# Siscom_Seguidor_1.net
KiCad netlist of a schematic drawn in EAGLE
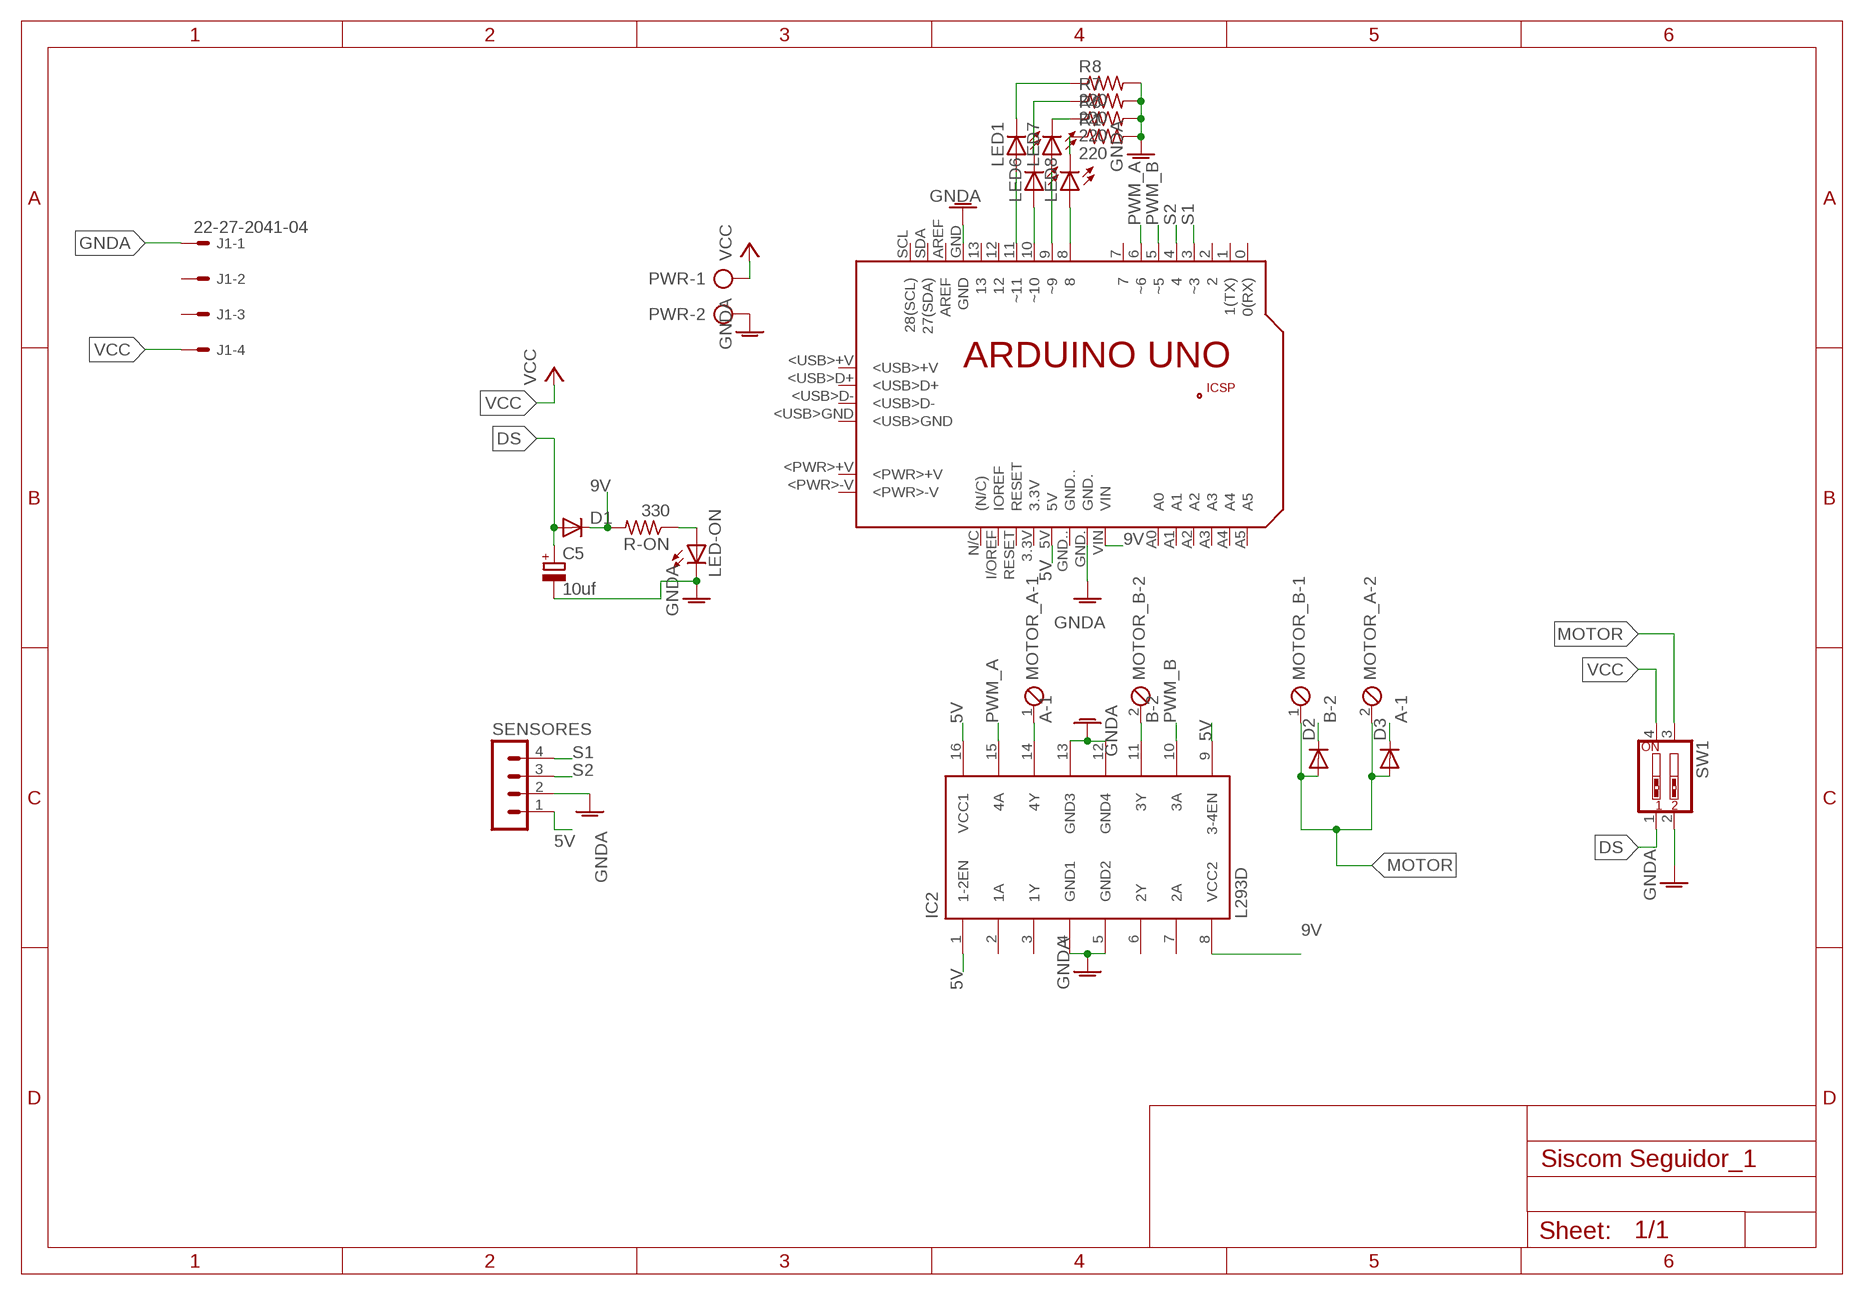
[diagram p0: schematic, sheet 1]

(export (version "E")
  (design (tool "Eeschema 10.0.6"))
  (components
    (comp (ref "C5")
      (value "10uf")
      (footprint "eagle-import:E2,5-6E")
      (libsource (lib "eagle-import") (part "CPOL-EUE2,5-6E"))
    )
    (comp (ref "D1")
      (value "1N4148DO35-7")
      (footprint "eagle-import:DO35-7")
      (libsource (lib "eagle-import") (part "1N4148DO35-7"))
    )
    (comp (ref "D2")
      (value "1N4148DO35-7")
      (footprint "eagle-import:DO35-7")
      (libsource (lib "eagle-import") (part "1N4148DO35-7"))
    )
    (comp (ref "D3")
      (value "1N4148DO35-7")
      (footprint "eagle-import:DO35-7")
      (libsource (lib "eagle-import") (part "1N4148DO35-7"))
    )
    (comp (ref "IC2")
      (value "L293D")
      (footprint "eagle-import:DIL16")
      (libsource (lib "eagle-import") (part "L293D"))
    )
    (comp (ref "J1")
      (value "22-27-2041-04")
      (footprint "eagle-import:6410-04")
      (libsource (lib "eagle-import") (part "22-?-0427-2041"))
    )
    (comp (ref "LED-ON")
      (value "LED3MM")
      (footprint "eagle-import:LED3MM")
      (libsource (lib "eagle-import") (part "LED3MM"))
    )
    (comp (ref "LED1")
      (value "LED3MM")
      (footprint "eagle-import:LED3MM")
      (libsource (lib "eagle-import") (part "LED3MM"))
    )
    (comp (ref "LED6")
      (value "LED3MM")
      (footprint "eagle-import:LED3MM")
      (libsource (lib "eagle-import") (part "LED3MM"))
    )
    (comp (ref "LED7")
      (value "LED3MM")
      (footprint "eagle-import:LED3MM")
      (libsource (lib "eagle-import") (part "LED3MM"))
    )
    (comp (ref "LED8")
      (value "LED3MM")
      (footprint "eagle-import:LED3MM")
      (libsource (lib "eagle-import") (part "LED3MM"))
    )
    (comp (ref "MOTOR_A")
      (value "MPT2")
      (footprint "eagle-import:2POL254")
      (libsource (lib "eagle-import") (part "MPT2"))
    )
    (comp (ref "MOTOR_B")
      (value "MPT2")
      (footprint "eagle-import:2POL254")
      (libsource (lib "eagle-import") (part "MPT2"))
    )
    (comp (ref "PCB2")
      (value "ARDUINO_UNO")
      (footprint "eagle-import:ARDUINO_UNO")
      (libsource (lib "eagle-import") (part "ARDUINO_UNO"))
    )
    (comp (ref "PWR")
      (value "AK500/2")
      (footprint "eagle-import:AK500_2")
      (libsource (lib "eagle-import") (part "AK500/2"))
    )
    (comp (ref "R-ON")
      (value "330")
      (footprint "eagle-import:0204_7")
      (libsource (lib "eagle-import") (part "R-US_0204/7"))
    )
    (comp (ref "R1")
      (value "220")
      (footprint "eagle-import:0204_7")
      (libsource (lib "eagle-import") (part "R-US_0204/7"))
    )
    (comp (ref "R6")
      (value "220")
      (footprint "eagle-import:0204_7")
      (libsource (lib "eagle-import") (part "R-US_0204/7"))
    )
    (comp (ref "R7")
      (value "220")
      (footprint "eagle-import:0204_7")
      (libsource (lib "eagle-import") (part "R-US_0204/7"))
    )
    (comp (ref "R8")
      (value "220")
      (footprint "eagle-import:0204_7")
      (libsource (lib "eagle-import") (part "R-US_0204/7"))
    )
    (comp (ref "SENSORES")
      (value "MA04-1")
      (footprint "eagle-import:MA04-1")
      (libsource (lib "eagle-import") (part "MA04-1"))
    )
    (comp (ref "SW1")
      (value "SW_DIP-2")
      (footprint "eagle-import:EDG-02")
      (libsource (lib "eagle-import") (part "SW_DIP-2"))
    )
  )
  (nets
    (net (code "1") (name "/5V") (class "Default")
      (node (ref "IC2") (pin "1") (pinfunction "1-2EN_1") (pintype "input"))
      (node (ref "IC2") (pin "16") (pinfunction "VCC1_16") (pintype "power_in"))
      (node (ref "IC2") (pin "9") (pinfunction "3-4EN_9") (pintype "input"))
      (node (ref "PCB2") (pin "5V") (pinfunction "5V_5V") (pintype "bidirectional"))
      (node (ref "SENSORES") (pin "1") (pinfunction "1_1") (pintype "passive"))
    )
    (net (code "2") (name "/9V") (class "Default")
      (node (ref "D1") (pin "C") (pinfunction "C_C") (pintype "passive"))
      (node (ref "IC2") (pin "8") (pinfunction "VCC2_8") (pintype "power_in"))
      (node (ref "PCB2") (pin "VIN") (pinfunction "VIN_VIN") (pintype "bidirectional"))
      (node (ref "R-ON") (pin "2") (pinfunction "2_2") (pintype "passive"))
    )
    (net (code "3") (name "/A-1") (class "Default")
      (node (ref "D3") (pin "C") (pinfunction "C_C") (pintype "passive"))
      (node (ref "IC2") (pin "14") (pinfunction "4Y_14") (pintype "output"))
      (node (ref "MOTOR_A") (pin "1") (pinfunction "1_1") (pintype "passive"))
    )
    (net (code "4") (name "/B-2") (class "Default")
      (node (ref "D2") (pin "C") (pinfunction "C_C") (pintype "passive"))
      (node (ref "IC2") (pin "11") (pinfunction "3Y_11") (pintype "output"))
      (node (ref "MOTOR_B") (pin "2") (pinfunction "1_2") (pintype "passive"))
    )
    (net (code "5") (name "/PWM_A") (class "Default")
      (node (ref "IC2") (pin "15") (pinfunction "4A_15") (pintype "input"))
      (node (ref "PCB2") (pin "6") (pinfunction "~{6}_6") (pintype "bidirectional"))
    )
    (net (code "6") (name "/PWM_B") (class "Default")
      (node (ref "IC2") (pin "10") (pinfunction "3A_10") (pintype "input"))
      (node (ref "PCB2") (pin "5") (pinfunction "~{5}_5") (pintype "bidirectional"))
    )
    (net (code "7") (name "/S1") (class "Default")
      (node (ref "PCB2") (pin "3") (pinfunction "~{3}_3") (pintype "bidirectional"))
      (node (ref "SENSORES") (pin "4") (pinfunction "4_4") (pintype "passive"))
    )
    (net (code "8") (name "/S2") (class "Default")
      (node (ref "PCB2") (pin "4") (pinfunction "4_4") (pintype "bidirectional"))
      (node (ref "SENSORES") (pin "3") (pinfunction "3_3") (pintype "passive"))
    )
    (net (code "9") (name "DS") (class "Default")
      (node (ref "C5") (pin "+") (pinfunction "+_+") (pintype "passive"))
      (node (ref "D1") (pin "A") (pinfunction "A_A") (pintype "passive"))
      (node (ref "SW1") (pin "1") (pinfunction "1_1") (pintype "passive"))
    )
    (net (code "10") (name "GNDA") (class "Default")
      (node (ref "C5") (pin "-") (pinfunction "-_-") (pintype "passive"))
      (node (ref "IC2") (pin "12") (pinfunction "GND4_12") (pintype "power_in"))
      (node (ref "IC2") (pin "13") (pinfunction "GND3_13") (pintype "power_in"))
      (node (ref "IC2") (pin "4") (pinfunction "GND1_4") (pintype "power_in"))
      (node (ref "IC2") (pin "5") (pinfunction "GND2_5") (pintype "power_in"))
      (node (ref "J1") (pin "1") (pinfunction "S_1") (pintype "passive"))
      (node (ref "LED-ON") (pin "K") (pinfunction "C_K") (pintype "passive"))
      (node (ref "PCB2") (pin "GND") (pinfunction "GND_GND") (pintype "bidirectional"))
      (node (ref "PCB2") (pin "GND.") (pinfunction "GND._GND.") (pintype "bidirectional"))
      (node (ref "PWR") (pin "2") (pinfunction "KL_2") (pintype "passive"))
      (node (ref "R1") (pin "2") (pinfunction "2_2") (pintype "passive"))
      (node (ref "R6") (pin "2") (pinfunction "2_2") (pintype "passive"))
      (node (ref "R7") (pin "2") (pinfunction "2_2") (pintype "passive"))
      (node (ref "R8") (pin "2") (pinfunction "2_2") (pintype "passive"))
      (node (ref "SENSORES") (pin "2") (pinfunction "2_2") (pintype "passive"))
      (node (ref "SW1") (pin "2") (pinfunction "2_2") (pintype "passive"))
    )
    (net (code "11") (name "MOTOR") (class "Default")
      (node (ref "D2") (pin "A") (pinfunction "A_A") (pintype "passive"))
      (node (ref "D3") (pin "A") (pinfunction "A_A") (pintype "passive"))
      (node (ref "MOTOR_A") (pin "2") (pinfunction "1_2") (pintype "passive"))
      (node (ref "MOTOR_B") (pin "1") (pinfunction "1_1") (pintype "passive"))
      (node (ref "SW1") (pin "3") (pinfunction "3_3") (pintype "passive"))
    )
    (net (code "12") (name "Net-(LED-ON-PadA)") (class "Default")
      (node (ref "LED-ON") (pin "A") (pinfunction "A_A") (pintype "passive"))
      (node (ref "R-ON") (pin "1") (pinfunction "1_1") (pintype "passive"))
    )
    (net (code "13") (name "Net-(LED1-C)") (class "Default")
      (node (ref "LED1") (pin "K") (pinfunction "C_K") (pintype "passive"))
      (node (ref "R8") (pin "1") (pinfunction "1_1") (pintype "passive"))
    )
    (net (code "14") (name "Net-(LED6-C)") (class "Default")
      (node (ref "LED6") (pin "K") (pinfunction "C_K") (pintype "passive"))
      (node (ref "R7") (pin "1") (pinfunction "1_1") (pintype "passive"))
    )
    (net (code "15") (name "Net-(LED7-C)") (class "Default")
      (node (ref "LED7") (pin "K") (pinfunction "C_K") (pintype "passive"))
      (node (ref "R6") (pin "1") (pinfunction "1_1") (pintype "passive"))
    )
    (net (code "16") (name "Net-(LED8-C)") (class "Default")
      (node (ref "LED8") (pin "K") (pinfunction "C_K") (pintype "passive"))
      (node (ref "R1") (pin "1") (pinfunction "1_1") (pintype "passive"))
    )
    (net (code "17") (name "Net-(LED8-PadA)") (class "Default")
      (node (ref "LED8") (pin "A") (pinfunction "A_A") (pintype "passive"))
      (node (ref "PCB2") (pin "8") (pinfunction "8_8") (pintype "bidirectional"))
    )
    (net (code "18") (name "Net-(PCB2-~{9})") (class "Default")
      (node (ref "LED7") (pin "A") (pinfunction "A_A") (pintype "passive"))
      (node (ref "PCB2") (pin "9") (pinfunction "~{9}_9") (pintype "bidirectional"))
    )
    (net (code "19") (name "Net-(PCB2-~{10})") (class "Default")
      (node (ref "LED6") (pin "A") (pinfunction "A_A") (pintype "passive"))
      (node (ref "PCB2") (pin "10") (pinfunction "~{10}_10") (pintype "bidirectional"))
    )
    (net (code "20") (name "Net-(PCB2-~{11})") (class "Default")
      (node (ref "LED1") (pin "A") (pinfunction "A_A") (pintype "passive"))
      (node (ref "PCB2") (pin "11") (pinfunction "~{11}_11") (pintype "bidirectional"))
    )
    (net (code "21") (name "VCC") (class "Default")
      (node (ref "J1") (pin "4") (pinfunction "S_4") (pintype "passive"))
      (node (ref "PWR") (pin "1") (pinfunction "KL_1") (pintype "passive"))
      (node (ref "SW1") (pin "4") (pinfunction "4_4") (pintype "passive"))
    )
    (net (code "22") (name "unconnected-(IC2-1A-Pad2)") (class "Default")
      (node (ref "IC2") (pin "2") (pinfunction "1A_2") (pintype "input"))
    )
    (net (code "23") (name "unconnected-(IC2-1Y-Pad3)") (class "Default")
      (node (ref "IC2") (pin "3") (pinfunction "1Y_3") (pintype "output"))
    )
    (net (code "24") (name "unconnected-(IC2-2A-Pad7)") (class "Default")
      (node (ref "IC2") (pin "7") (pinfunction "2A_7") (pintype "input"))
    )
    (net (code "25") (name "unconnected-(IC2-2Y-Pad6)") (class "Default")
      (node (ref "IC2") (pin "6") (pinfunction "2Y_6") (pintype "output"))
    )
    (net (code "26") (name "unconnected-(J1B-S-Pad2)") (class "Default")
      (node (ref "J1") (pin "2") (pinfunction "S_2") (pintype "passive"))
    )
    (net (code "27") (name "unconnected-(J1C-S-Pad3)") (class "Default")
      (node (ref "J1") (pin "3") (pinfunction "S_3") (pintype "passive"))
    )
    (net (code "28") (name "unconnected-(PCB2-(N{slash}C)-PadN{slash}C)") (class "Default")
      (node (ref "PCB2") (pin "N/C") (pinfunction "(N/C)_N/C") (pintype "bidirectional"))
    )
    (net (code "29") (name "unconnected-(PCB2-0(RX)-Pad0)") (class "Default")
      (node (ref "PCB2") (pin "0") (pinfunction "0(RX)_0") (pintype "bidirectional"))
    )
    (net (code "30") (name "unconnected-(PCB2-1(TX)-Pad1)") (class "Default")
      (node (ref "PCB2") (pin "1") (pinfunction "1(TX)_1") (pintype "bidirectional"))
    )
    (net (code "31") (name "unconnected-(PCB2-27(SDA)-PadSDA)") (class "Default")
      (node (ref "PCB2") (pin "SDA") (pinfunction "27(SDA)_SDA") (pintype "bidirectional"))
    )
    (net (code "32") (name "unconnected-(PCB2-28(SCL)-PadSCL)") (class "Default")
      (node (ref "PCB2") (pin "SCL") (pinfunction "28(SCL)_SCL") (pintype "bidirectional"))
    )
    (net (code "33") (name "unconnected-(PCB2-IOREF-PadI{slash}OREF)") (class "Default")
      (node (ref "PCB2") (pin "I/OREF") (pinfunction "IOREF_I/OREF") (pintype "bidirectional"))
    )
    (net (code "34") (name "unconnected-(PCB2-Pad+5V)") (class "Default")
      (node (ref "PCB2") (pin "+5V") (pinfunction "+5V_+5V") (pintype "bidirectional"))
    )
    (net (code "35") (name "unconnected-(PCB2-Pad2)") (class "Default")
      (node (ref "PCB2") (pin "2") (pinfunction "2_2") (pintype "bidirectional"))
    )
    (net (code "36") (name "unconnected-(PCB2-Pad3.3V)") (class "Default")
      (node (ref "PCB2") (pin "3.3V") (pinfunction "3.3V_3.3V") (pintype "bidirectional"))
    )
    (net (code "37") (name "unconnected-(PCB2-Pad7)") (class "Default")
      (node (ref "PCB2") (pin "7") (pinfunction "7_7") (pintype "bidirectional"))
    )
    (net (code "38") (name "unconnected-(PCB2-Pad12)") (class "Default")
      (node (ref "PCB2") (pin "12") (pinfunction "12_12") (pintype "bidirectional"))
    )
    (net (code "39") (name "unconnected-(PCB2-Pad13)") (class "Default")
      (node (ref "PCB2") (pin "13") (pinfunction "13_13") (pintype "bidirectional"))
    )
    (net (code "40") (name "unconnected-(PCB2-Pad<PWR>+V)") (class "Default")
      (node (ref "PCB2") (pin "<PWR>+V") (pinfunction "<PWR>+V_<PWR>+V") (pintype "bidirectional"))
    )
    (net (code "41") (name "unconnected-(PCB2-Pad<PWR>-V)") (class "Default")
      (node (ref "PCB2") (pin "<PWR>-V") (pinfunction "<PWR>-V_<PWR>-V") (pintype "bidirectional"))
    )
    (net (code "42") (name "unconnected-(PCB2-Pad<USB>+V)") (class "Default")
      (node (ref "PCB2") (pin "<USB>+V") (pinfunction "<USB>+V_<USB>+V") (pintype "bidirectional"))
    )
    (net (code "43") (name "unconnected-(PCB2-Pad<USB>D+)") (class "Default")
      (node (ref "PCB2") (pin "<USB>D+") (pinfunction "<USB>D+_<USB>D+") (pintype "bidirectional"))
    )
    (net (code "44") (name "unconnected-(PCB2-Pad<USB>D-)") (class "Default")
      (node (ref "PCB2") (pin "<USB>D-") (pinfunction "<USB>D-_<USB>D-") (pintype "bidirectional"))
    )
    (net (code "45") (name "unconnected-(PCB2-Pad<USB>GND)") (class "Default")
      (node (ref "PCB2") (pin "<USB>GND") (pinfunction "<USB>GND_<USB>GND") (pintype "bidirectional"))
    )
    (net (code "46") (name "unconnected-(PCB2-PadA0)") (class "Default")
      (node (ref "PCB2") (pin "A0") (pinfunction "A0_A0") (pintype "bidirectional"))
    )
    (net (code "47") (name "unconnected-(PCB2-PadA1)") (class "Default")
      (node (ref "PCB2") (pin "A1") (pinfunction "A1_A1") (pintype "bidirectional"))
    )
    (net (code "48") (name "unconnected-(PCB2-PadA2)") (class "Default")
      (node (ref "PCB2") (pin "A2") (pinfunction "A2_A2") (pintype "bidirectional"))
    )
    (net (code "49") (name "unconnected-(PCB2-PadA3)") (class "Default")
      (node (ref "PCB2") (pin "A3") (pinfunction "A3_A3") (pintype "bidirectional"))
    )
    (net (code "50") (name "unconnected-(PCB2-PadA4)") (class "Default")
      (node (ref "PCB2") (pin "A4") (pinfunction "A4_A4") (pintype "bidirectional"))
    )
    (net (code "51") (name "unconnected-(PCB2-PadA5)") (class "Default")
      (node (ref "PCB2") (pin "A5") (pinfunction "A5_A5") (pintype "bidirectional"))
    )
    (net (code "52") (name "unconnected-(PCB2-PadAREF)") (class "Default")
      (node (ref "PCB2") (pin "AREF") (pinfunction "AREF_AREF") (pintype "bidirectional"))
    )
    (net (code "53") (name "unconnected-(PCB2-PadGND..)") (class "Default")
      (node (ref "PCB2") (pin "GND..") (pinfunction "GND.._GND..") (pintype "bidirectional"))
    )
    (net (code "54") (name "unconnected-(PCB2-PadGND_)") (class "Default")
      (node (ref "PCB2") (pin "GND_") (pinfunction "GND__GND_") (pintype "bidirectional"))
    )
    (net (code "55") (name "unconnected-(PCB2-PadMISO)") (class "Default")
      (node (ref "PCB2") (pin "MISO") (pinfunction "MISO_MISO") (pintype "bidirectional"))
    )
    (net (code "56") (name "unconnected-(PCB2-PadMOSI)") (class "Default")
      (node (ref "PCB2") (pin "MOSI") (pinfunction "MOSI_MOSI") (pintype "bidirectional"))
    )
    (net (code "57") (name "unconnected-(PCB2-PadRESET)") (class "Default")
      (node (ref "PCB2") (pin "RESET") (pinfunction "RESET_RESET") (pintype "bidirectional"))
    )
    (net (code "58") (name "unconnected-(PCB2-PadRESET.)") (class "Default")
      (node (ref "PCB2") (pin "RESET.") (pinfunction "RESET._RESET.") (pintype "bidirectional"))
    )
    (net (code "59") (name "unconnected-(PCB2-PadSCK)") (class "Default")
      (node (ref "PCB2") (pin "SCK") (pinfunction "SCK_SCK") (pintype "bidirectional"))
    )
  )
)
